# OSSI-1_Front_Panel.net
KiCad netlist of a schematic drawn in Altium Designer
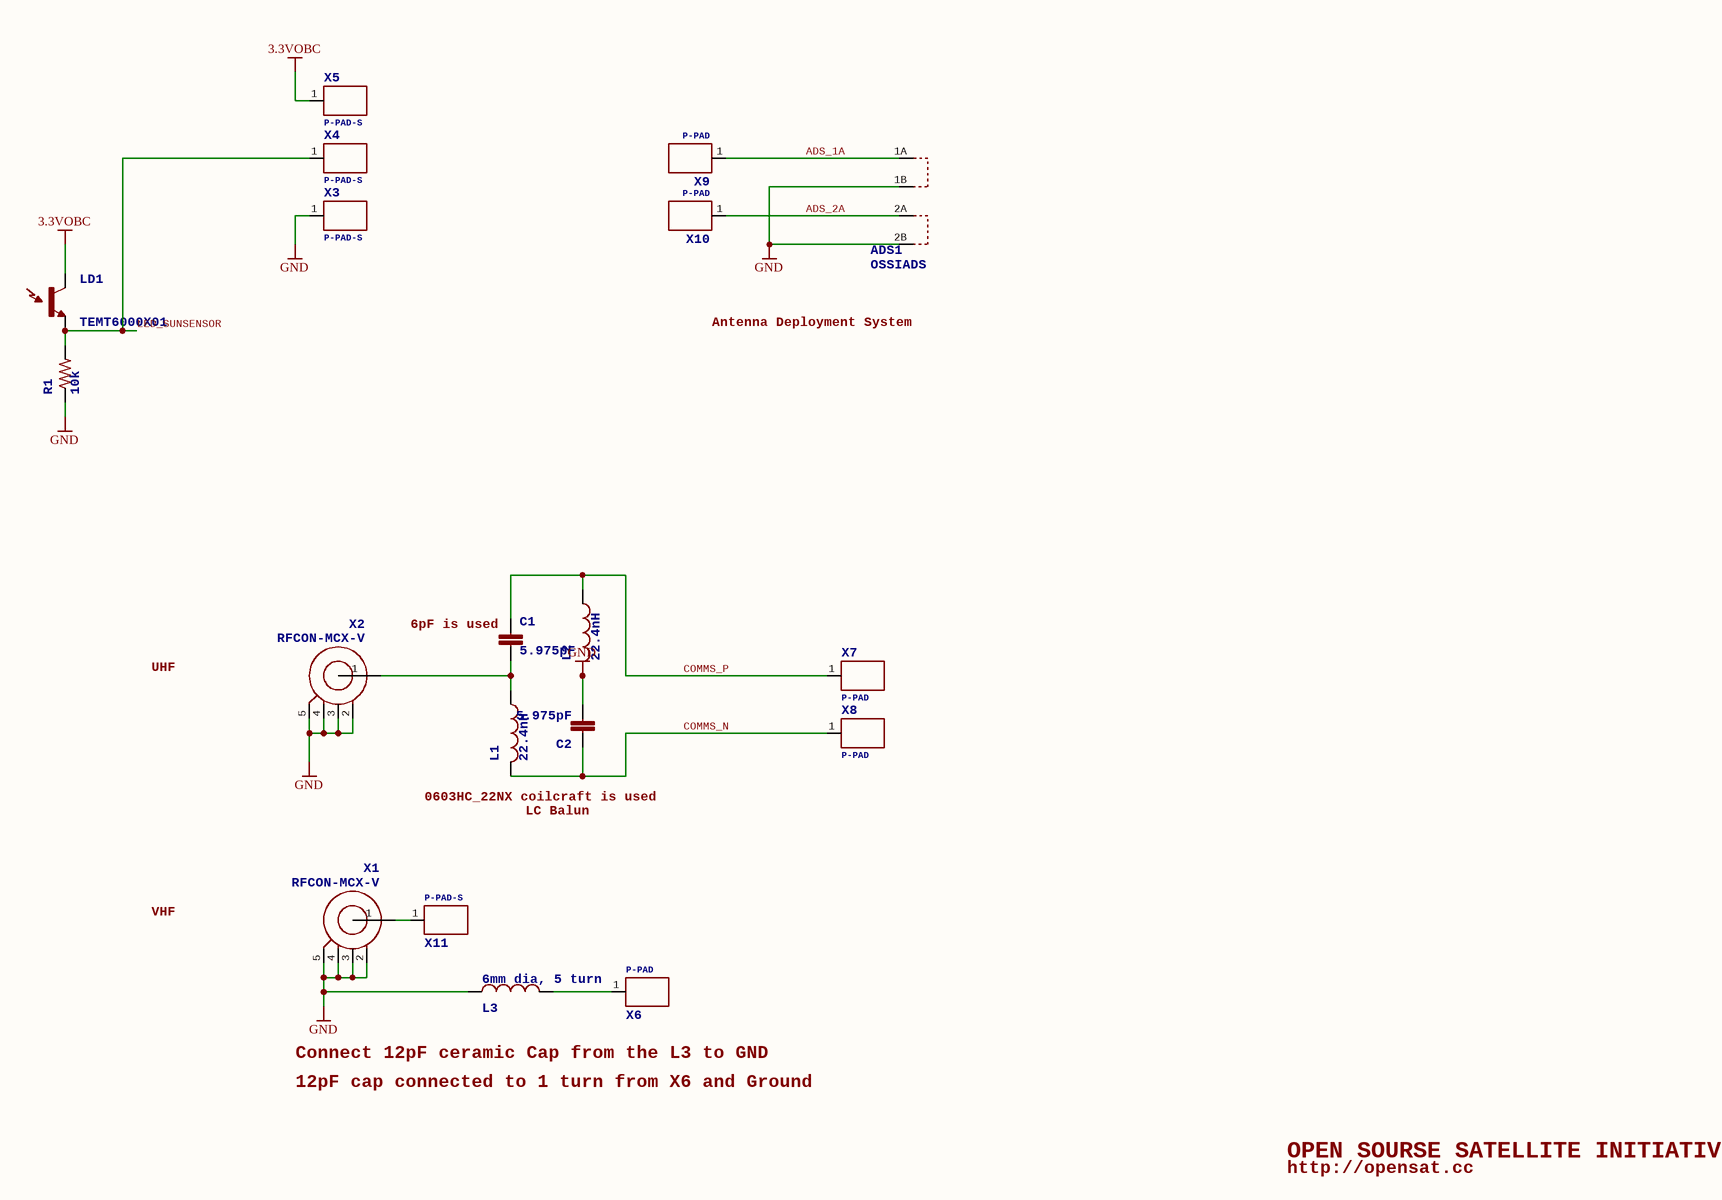
[diagram p0: OSSI-1 Front Panel.SchDoc]

(export (version "E")
  (design (tool "Eeschema 10.0.6"))
  (components
    (comp (ref "ADS1")
      (value "OSSIADS")
      (footprint "OSSIADS")
      (fields (field (name ">NAME") "ADS1") (field (name ">VALUE") "OSSIADS"))
      (libsource (lib "OSSI") (part "OSSIADS"))
    )
    (comp (ref "C1")
      (value "5.975pF")
      (footprint "C0805(2012)")
      (fields (field (name ">NAME") "C1") (field (name ">VALUE") "5.975pF"))
      (libsource (lib "OSSI") (part "C0805(2012)"))
    )
    (comp (ref "C2")
      (value "5.975pF")
      (footprint "C0805(2012)")
      (fields (field (name ">NAME") "C2") (field (name ">VALUE") "5.975pF"))
      (libsource (lib "") (part "C0805(2012)_1"))
    )
    (comp (ref "L1")
      (value "22.4nH")
      (footprint "L0805(2012)")
      (fields (field (name ">NAME") "L1") (field (name ">VALUE") "22.4nH"))
      (libsource (lib "OSSI") (part "L0805(2012)"))
    )
    (comp (ref "L2")
      (value "22.4nH")
      (footprint "L0805(2012)")
      (fields (field (name ">NAME") "L2") (field (name ">VALUE") "22.4nH"))
      (libsource (lib "OSSI") (part "L0805(2012)"))
    )
    (comp (ref "L3")
      (value "6mm dia, 5 turn")
      (footprint "0207/10")
      (description "<B>INDUCTOR</B>, American symbol")
      (fields (field (name ">NAME") "L3") (field (name ">VALUE") "6mm dia, 5 turn"))
      (libsource (lib "rcl") (part "L-US0207/10"))
    )
    (comp (ref "LD1")
      (value "TEMT6000X01")
      (footprint "TEMT6000-SEN")
      (fields (field (name ">VALUE") "TEMT6000X01") (field (name ">NAME") "LD1"))
      (libsource (lib "OSSI") (part "TEMT6000X01"))
    )
    (comp (ref "R1")
      (value "10k")
      (footprint "R0805(2012)")
      (fields (field (name ">NAME") "R1") (field (name ">VALUE") "10k"))
      (libsource (lib "OSSI") (part "R0805(2012)"))
    )
    (comp (ref "X1")
      (value "RFCON-MCX-V")
      (footprint "MCX-V")
      (description "RF Connectors")
      (fields (field (name ">NAME") "X1") (field (name ">VALUE") "RFCON-MCX-V"))
      (libsource (lib "OSSI") (part "RFCON-MCX-V"))
    )
    (comp (ref "X2")
      (value "RFCON-MCX-V")
      (footprint "MCX-V")
      (description "RF Connectors")
      (fields (field (name ">NAME") "X2") (field (name ">VALUE") "RFCON-MCX-V"))
      (libsource (lib "OSSI") (part "RFCON-MCX-V"))
    )
    (comp (ref "X3")
      (value "P-PAD-S")
      (footprint "P-PAD-S")
      (fields (field (name ">NAME") "X3") (field (name ">VALUE") "P-PAD-S"))
      (libsource (lib "OSSI") (part "P-PAD-S"))
    )
    (comp (ref "X4")
      (value "P-PAD-S")
      (footprint "P-PAD-S")
      (fields (field (name ">NAME") "X4") (field (name ">VALUE") "P-PAD-S"))
      (libsource (lib "OSSI") (part "P-PAD-S"))
    )
    (comp (ref "X5")
      (value "P-PAD-S")
      (footprint "P-PAD-S")
      (fields (field (name ">NAME") "X5") (field (name ">VALUE") "P-PAD-S"))
      (libsource (lib "OSSI") (part "P-PAD-S"))
    )
    (comp (ref "X6")
      (value "P-PAD")
      (footprint "P-PAD")
      (fields (field (name ">NAME") "X6") (field (name ">VALUE") "P-PAD"))
      (libsource (lib "OSSI") (part "P-PAD"))
    )
    (comp (ref "X7")
      (value "P-PAD")
      (footprint "P-PAD")
      (fields (field (name ">NAME") "X7") (field (name ">VALUE") "P-PAD"))
      (libsource (lib "OSSI") (part "P-PAD"))
    )
    (comp (ref "X8")
      (value "P-PAD")
      (footprint "P-PAD")
      (fields (field (name ">NAME") "X8") (field (name ">VALUE") "P-PAD"))
      (libsource (lib "OSSI") (part "P-PAD"))
    )
    (comp (ref "X9")
      (value "P-PAD")
      (footprint "P-PAD")
      (fields (field (name ">NAME") "X9") (field (name ">VALUE") "P-PAD"))
      (libsource (lib "OSSI") (part "P-PAD"))
    )
    (comp (ref "X10")
      (value "P-PAD")
      (footprint "P-PAD")
      (fields (field (name ">NAME") "X10") (field (name ">VALUE") "P-PAD"))
      (libsource (lib "OSSI") (part "P-PAD"))
    )
    (comp (ref "X11")
      (value "P-PAD-S")
      (footprint "P-PAD-S")
      (fields (field (name ">NAME") "X11") (field (name ">VALUE") "P-PAD-S"))
      (libsource (lib "OSSI") (part "P-PAD-S"))
    )
  )
  (nets
    (net (code "1") (name "/ADS_1A") (class "Default")
      (node (ref "ADS1") (pin "1A") (pinfunction "1A_1A") (pintype "passive"))
      (node (ref "X9") (pin "1") (pinfunction "P$1_1") (pintype "passive"))
    )
    (net (code "2") (name "/ADS_2A") (class "Default")
      (node (ref "ADS1") (pin "2A") (pinfunction "2A_2A") (pintype "passive"))
      (node (ref "X10") (pin "1") (pinfunction "P$1_1") (pintype "passive"))
    )
    (net (code "3") (name "/COMMS_N") (class "Default")
      (node (ref "C2") (pin "1") (pinfunction "1_1") (pintype "passive"))
      (node (ref "L1") (pin "2") (pinfunction "2_2") (pintype "passive"))
      (node (ref "X8") (pin "1") (pinfunction "P$1_1") (pintype "passive"))
    )
    (net (code "4") (name "/COMMS_P") (class "Default")
      (node (ref "C1") (pin "1") (pinfunction "1_1") (pintype "passive"))
      (node (ref "L2") (pin "1") (pinfunction "1_1") (pintype "passive"))
      (node (ref "X7") (pin "1") (pinfunction "P$1_1") (pintype "passive"))
    )
    (net (code "5") (name "/LED_SUNSENSOR") (class "Default")
      (node (ref "LD1") (pin "EMITTER") (pinfunction "E1_EMITTER") (pintype "passive"))
      (node (ref "R1") (pin "2") (pinfunction "2_2") (pintype "passive"))
      (node (ref "X4") (pin "1") (pinfunction "P$1_1") (pintype "passive"))
    )
    (net (code "6") (name "3.3VOBC") (class "Default")
      (node (ref "LD1") (pin "COLLECTOR") (pinfunction "C1_COLLECTOR") (pintype "passive"))
      (node (ref "X5") (pin "1") (pinfunction "P$1_1") (pintype "passive"))
    )
    (net (code "7") (name "GND") (class "Default")
      (node (ref "ADS1") (pin "1B") (pinfunction "1B_1B") (pintype "passive"))
      (node (ref "ADS1") (pin "2B") (pinfunction "2B_2B") (pintype "passive"))
      (node (ref "C2") (pin "2") (pinfunction "2_2") (pintype "passive"))
      (node (ref "L2") (pin "2") (pinfunction "2_2") (pintype "passive"))
      (node (ref "L3") (pin "2") (pinfunction "2_2") (pintype "passive"))
      (node (ref "R1") (pin "1") (pinfunction "1_1") (pintype "passive"))
      (node (ref "X1") (pin "2") (pinfunction "2_2") (pintype "open_emitter"))
      (node (ref "X1") (pin "3") (pinfunction "3_3") (pintype "open_emitter"))
      (node (ref "X1") (pin "4") (pinfunction "4_4") (pintype "open_emitter"))
      (node (ref "X1") (pin "5") (pinfunction "5_5") (pintype "open_emitter"))
      (node (ref "X2") (pin "2") (pinfunction "2_2") (pintype "open_emitter"))
      (node (ref "X2") (pin "3") (pinfunction "3_3") (pintype "open_emitter"))
      (node (ref "X2") (pin "4") (pinfunction "4_4") (pintype "open_emitter"))
      (node (ref "X2") (pin "5") (pinfunction "5_5") (pintype "open_emitter"))
      (node (ref "X3") (pin "1") (pinfunction "P$1_1") (pintype "passive"))
    )
    (net (code "8") (name "Net-(C1-Pad2)") (class "Default")
      (node (ref "C1") (pin "2") (pinfunction "2_2") (pintype "passive"))
      (node (ref "L1") (pin "1") (pinfunction "1_1") (pintype "passive"))
      (node (ref "X2") (pin "1") (pinfunction "1_1") (pintype "passive"))
    )
    (net (code "9") (name "Net-(X6-P$1)") (class "Default")
      (node (ref "L3") (pin "1") (pinfunction "1_1") (pintype "passive"))
      (node (ref "X6") (pin "1") (pinfunction "P$1_1") (pintype "passive"))
    )
    (net (code "10") (name "Net-(X11-P$1)") (class "Default")
      (node (ref "X1") (pin "1") (pinfunction "1_1") (pintype "passive"))
      (node (ref "X11") (pin "1") (pinfunction "P$1_1") (pintype "passive"))
    )
  )
)
